# 2_Sensors.net
KiCad netlist of a schematic drawn in Altium Designer
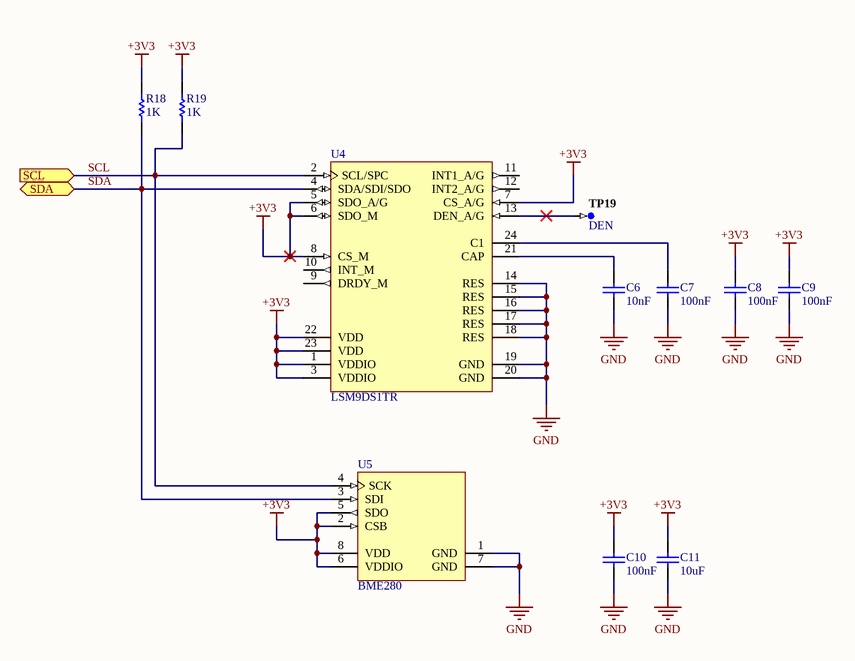
[diagram p0: 2_Sensors.SchDoc]

(export (version "E")
  (design (tool "Eeschema 10.0.6"))
  (components
    (comp (ref "C6")
      (value "10nF")
      (footprint "CAPC0603(1608)100_M")
      (description "CAP 10nF 25V ±5% 0603 (1608 Metric) Thickness 1mm SMD")
      (fields (field (name "TOLERANCE") "Â±5%"))
      (libsource (lib "Altium Content Vault") (part "CAP"))
    )
    (comp (ref "C7")
      (value "100nF")
      (footprint "CAPC0603(1608)100_M")
      (description "CAP 100nF 25V ±20% 0603 (1608 Metric) Thickness 1mm SMD")
      (fields (field (name "TOLERANCE") "Â±20%"))
      (libsource (lib "Altium Content Vault") (part "CAP"))
    )
    (comp (ref "C8")
      (value "100nF")
      (footprint "CAPC0603(1608)100_M")
      (description "CAP 100nF 25V ±20% 0603 (1608 Metric) Thickness 1mm SMD")
      (fields (field (name "TOLERANCE") "Â±20%"))
      (libsource (lib "Altium Content Vault") (part "CAP"))
    )
    (comp (ref "C9")
      (value "100nF")
      (footprint "CAPC0603(1608)100_M")
      (description "CAP 100nF 25V ±20% 0603 (1608 Metric) Thickness 1mm SMD")
      (fields (field (name "TOLERANCE") "Â±20%"))
      (libsource (lib "Altium Content Vault") (part "CAP"))
    )
    (comp (ref "C10")
      (value "100nF")
      (footprint "CAPC0603(1608)100_M")
      (description "CAP 100nF 25V ±20% 0603 (1608 Metric) Thickness 1mm SMD")
      (fields (field (name "TOLERANCE") "Â±20%"))
      (libsource (lib "Altium Content Vault") (part "CAP"))
    )
    (comp (ref "C11")
      (value "10uF")
      (footprint "CAPC1206(3216)130_L")
      (description "CAP 10uF 16V -20% to +80% 1206 (3216 Metric) Thickness 1.3mm SMD")
      (fields (field (name "TOLERANCE") "-20% to +80%"))
      (libsource (lib "Altium Content Vault") (part "CAP"))
    )
    (comp (ref "R18")
      (value "1K")
      (footprint "RESC0603(1608)_M")
      (description "1K 0.1W 1% 0603 (1608 Metric)  SMD")
      (fields (field (name "TOLERANCE") "1 %") (field (name "POWER") "0.1 W"))
      (libsource (lib "Altium Content Vault") (part "RES"))
    )
    (comp (ref "R19")
      (value "1K")
      (footprint "RESC0603(1608)_M")
      (description "1K 0.1W 1% 0603 (1608 Metric)  SMD")
      (fields (field (name "TOLERANCE") "1 %") (field (name "POWER") "0.1 W"))
      (libsource (lib "Altium Content Vault") (part "RES"))
    )
    (comp (ref "TP19")
      (value "DEN")
      (footprint "TP-SM-C-100")
      (description "Test Point, Surface Mount, Circular, Pad Diameter 1 mm")
      (fields (field (name "PARTNUMBER") "TP-SM-C-100") (field (name "MANUFACTURER") "No Vendor"))
      (libsource (lib "Altium Content Vault") (part "TP-SM"))
    )
    (comp (ref "U4")
      (value "LSM9DS1TR")
      (footprint "STM-LGA-24_3500X3000X1000")
      (fields (field (name "PARTNUMBER") "LSM9DS1") (field (name "MANUFACTURER") "STMicroelectronics"))
      (libsource (lib "Altium Content Vault") (part "STM-LSM9DS1-24"))
    )
    (comp (ref "U5")
      (value "BME280")
      (footprint "BOSC-BME280-8_V")
      (fields (field (name "MANUFACTURER") "Bosch Sensortec"))
      (libsource (lib "Altium Content Vault") (part "BOSC-BME280-8"))
    )
  )
  (nets
    (net (code "1") (name "+3V3") (class "Default")
      (node (ref "C10") (pin "1") (pinfunction "1_1") (pintype "passive"))
      (node (ref "C11") (pin "2") (pinfunction "2_2") (pintype "passive"))
      (node (ref "C8") (pin "1") (pinfunction "1_1") (pintype "passive"))
      (node (ref "C9") (pin "1") (pinfunction "1_1") (pintype "passive"))
      (node (ref "R18") (pin "2") (pinfunction "2_2") (pintype "passive"))
      (node (ref "R19") (pin "2") (pinfunction "2_2") (pintype "passive"))
      (node (ref "U4") (pin "1") (pinfunction "VDDIO_1") (pintype "power_in"))
      (node (ref "U4") (pin "22") (pinfunction "VDD_22") (pintype "power_in"))
      (node (ref "U4") (pin "23") (pinfunction "VDD_23") (pintype "power_in"))
      (node (ref "U4") (pin "3") (pinfunction "VDDIO_3") (pintype "power_in"))
      (node (ref "U4") (pin "5") (pinfunction "SDO_A/G_5") (pintype "bidirectional"))
      (node (ref "U4") (pin "6") (pinfunction "SDO_M_6") (pintype "bidirectional"))
      (node (ref "U4") (pin "7") (pinfunction "CS_A/G_7") (pintype "input"))
      (node (ref "U4") (pin "8") (pinfunction "CS_M_8") (pintype "input"))
      (node (ref "U5") (pin "2") (pinfunction "CSB_2") (pintype "input"))
      (node (ref "U5") (pin "5") (pinfunction "SDO_5") (pintype "output"))
      (node (ref "U5") (pin "6") (pinfunction "VDDIO_6") (pintype "power_in"))
      (node (ref "U5") (pin "8") (pinfunction "VDD_8") (pintype "power_in"))
    )
    (net (code "2") (name "/SCL") (class "Default")
      (node (ref "R19") (pin "1") (pinfunction "1_1") (pintype "passive"))
      (node (ref "U4") (pin "2") (pinfunction "SCL/SPC_2") (pintype "input"))
      (node (ref "U5") (pin "4") (pinfunction "SCK_4") (pintype "input"))
    )
    (net (code "3") (name "/SDA") (class "Default")
      (node (ref "R18") (pin "1") (pinfunction "1_1") (pintype "passive"))
      (node (ref "U4") (pin "4") (pinfunction "SDA/SDI/SDO_4") (pintype "bidirectional"))
      (node (ref "U5") (pin "3") (pinfunction "SDI_3") (pintype "input"))
    )
    (net (code "4") (name "GND") (class "Default")
      (node (ref "C10") (pin "2") (pinfunction "2_2") (pintype "passive"))
      (node (ref "C11") (pin "1") (pinfunction "1_1") (pintype "passive"))
      (node (ref "C6") (pin "1") (pinfunction "1_1") (pintype "passive"))
      (node (ref "C7") (pin "2") (pinfunction "2_2") (pintype "passive"))
      (node (ref "C8") (pin "2") (pinfunction "2_2") (pintype "passive"))
      (node (ref "C9") (pin "2") (pinfunction "2_2") (pintype "passive"))
      (node (ref "U4") (pin "14") (pinfunction "RES_14") (pintype "passive"))
      (node (ref "U4") (pin "15") (pinfunction "RES_15") (pintype "passive"))
      (node (ref "U4") (pin "16") (pinfunction "RES_16") (pintype "passive"))
      (node (ref "U4") (pin "17") (pinfunction "RES_17") (pintype "passive"))
      (node (ref "U4") (pin "18") (pinfunction "RES_18") (pintype "passive"))
      (node (ref "U4") (pin "19") (pinfunction "GND_19") (pintype "power_in"))
      (node (ref "U4") (pin "20") (pinfunction "GND_20") (pintype "power_in"))
      (node (ref "U5") (pin "1") (pinfunction "GND_1") (pintype "power_in"))
      (node (ref "U5") (pin "7") (pinfunction "GND_7") (pintype "power_in"))
    )
    (net (code "5") (name "Net-(U4-C1)") (class "Default")
      (node (ref "C7") (pin "1") (pinfunction "1_1") (pintype "passive"))
      (node (ref "U4") (pin "24") (pinfunction "C1_24") (pintype "passive"))
    )
    (net (code "6") (name "Net-(U4-CAP)") (class "Default")
      (node (ref "C6") (pin "2") (pinfunction "2_2") (pintype "passive"))
      (node (ref "U4") (pin "21") (pinfunction "CAP_21") (pintype "passive"))
    )
    (net (code "7") (name "Net-(U4-DEN_A{slash}G)") (class "Default")
      (node (ref "TP19") (pin "1") (pinfunction "1_1") (pintype "input"))
      (node (ref "U4") (pin "13") (pinfunction "DEN_A/G_13") (pintype "input"))
    )
    (net (code "8") (name "unconnected-(U4-DRDY_M-Pad9)") (class "Default")
      (node (ref "U4") (pin "9") (pinfunction "DRDY_M_9") (pintype "output"))
    )
    (net (code "9") (name "unconnected-(U4-INT1_A{slash}G-Pad11)") (class "Default")
      (node (ref "U4") (pin "11") (pinfunction "INT1_A/G_11") (pintype "output"))
    )
    (net (code "10") (name "unconnected-(U4-INT2_A{slash}G-Pad12)") (class "Default")
      (node (ref "U4") (pin "12") (pinfunction "INT2_A/G_12") (pintype "output"))
    )
    (net (code "11") (name "unconnected-(U4-INT_M-Pad10)") (class "Default")
      (node (ref "U4") (pin "10") (pinfunction "INT_M_10") (pintype "output"))
    )
  )
)
